# Power_Management.net
KiCad netlist of a schematic drawn in Altium Designer
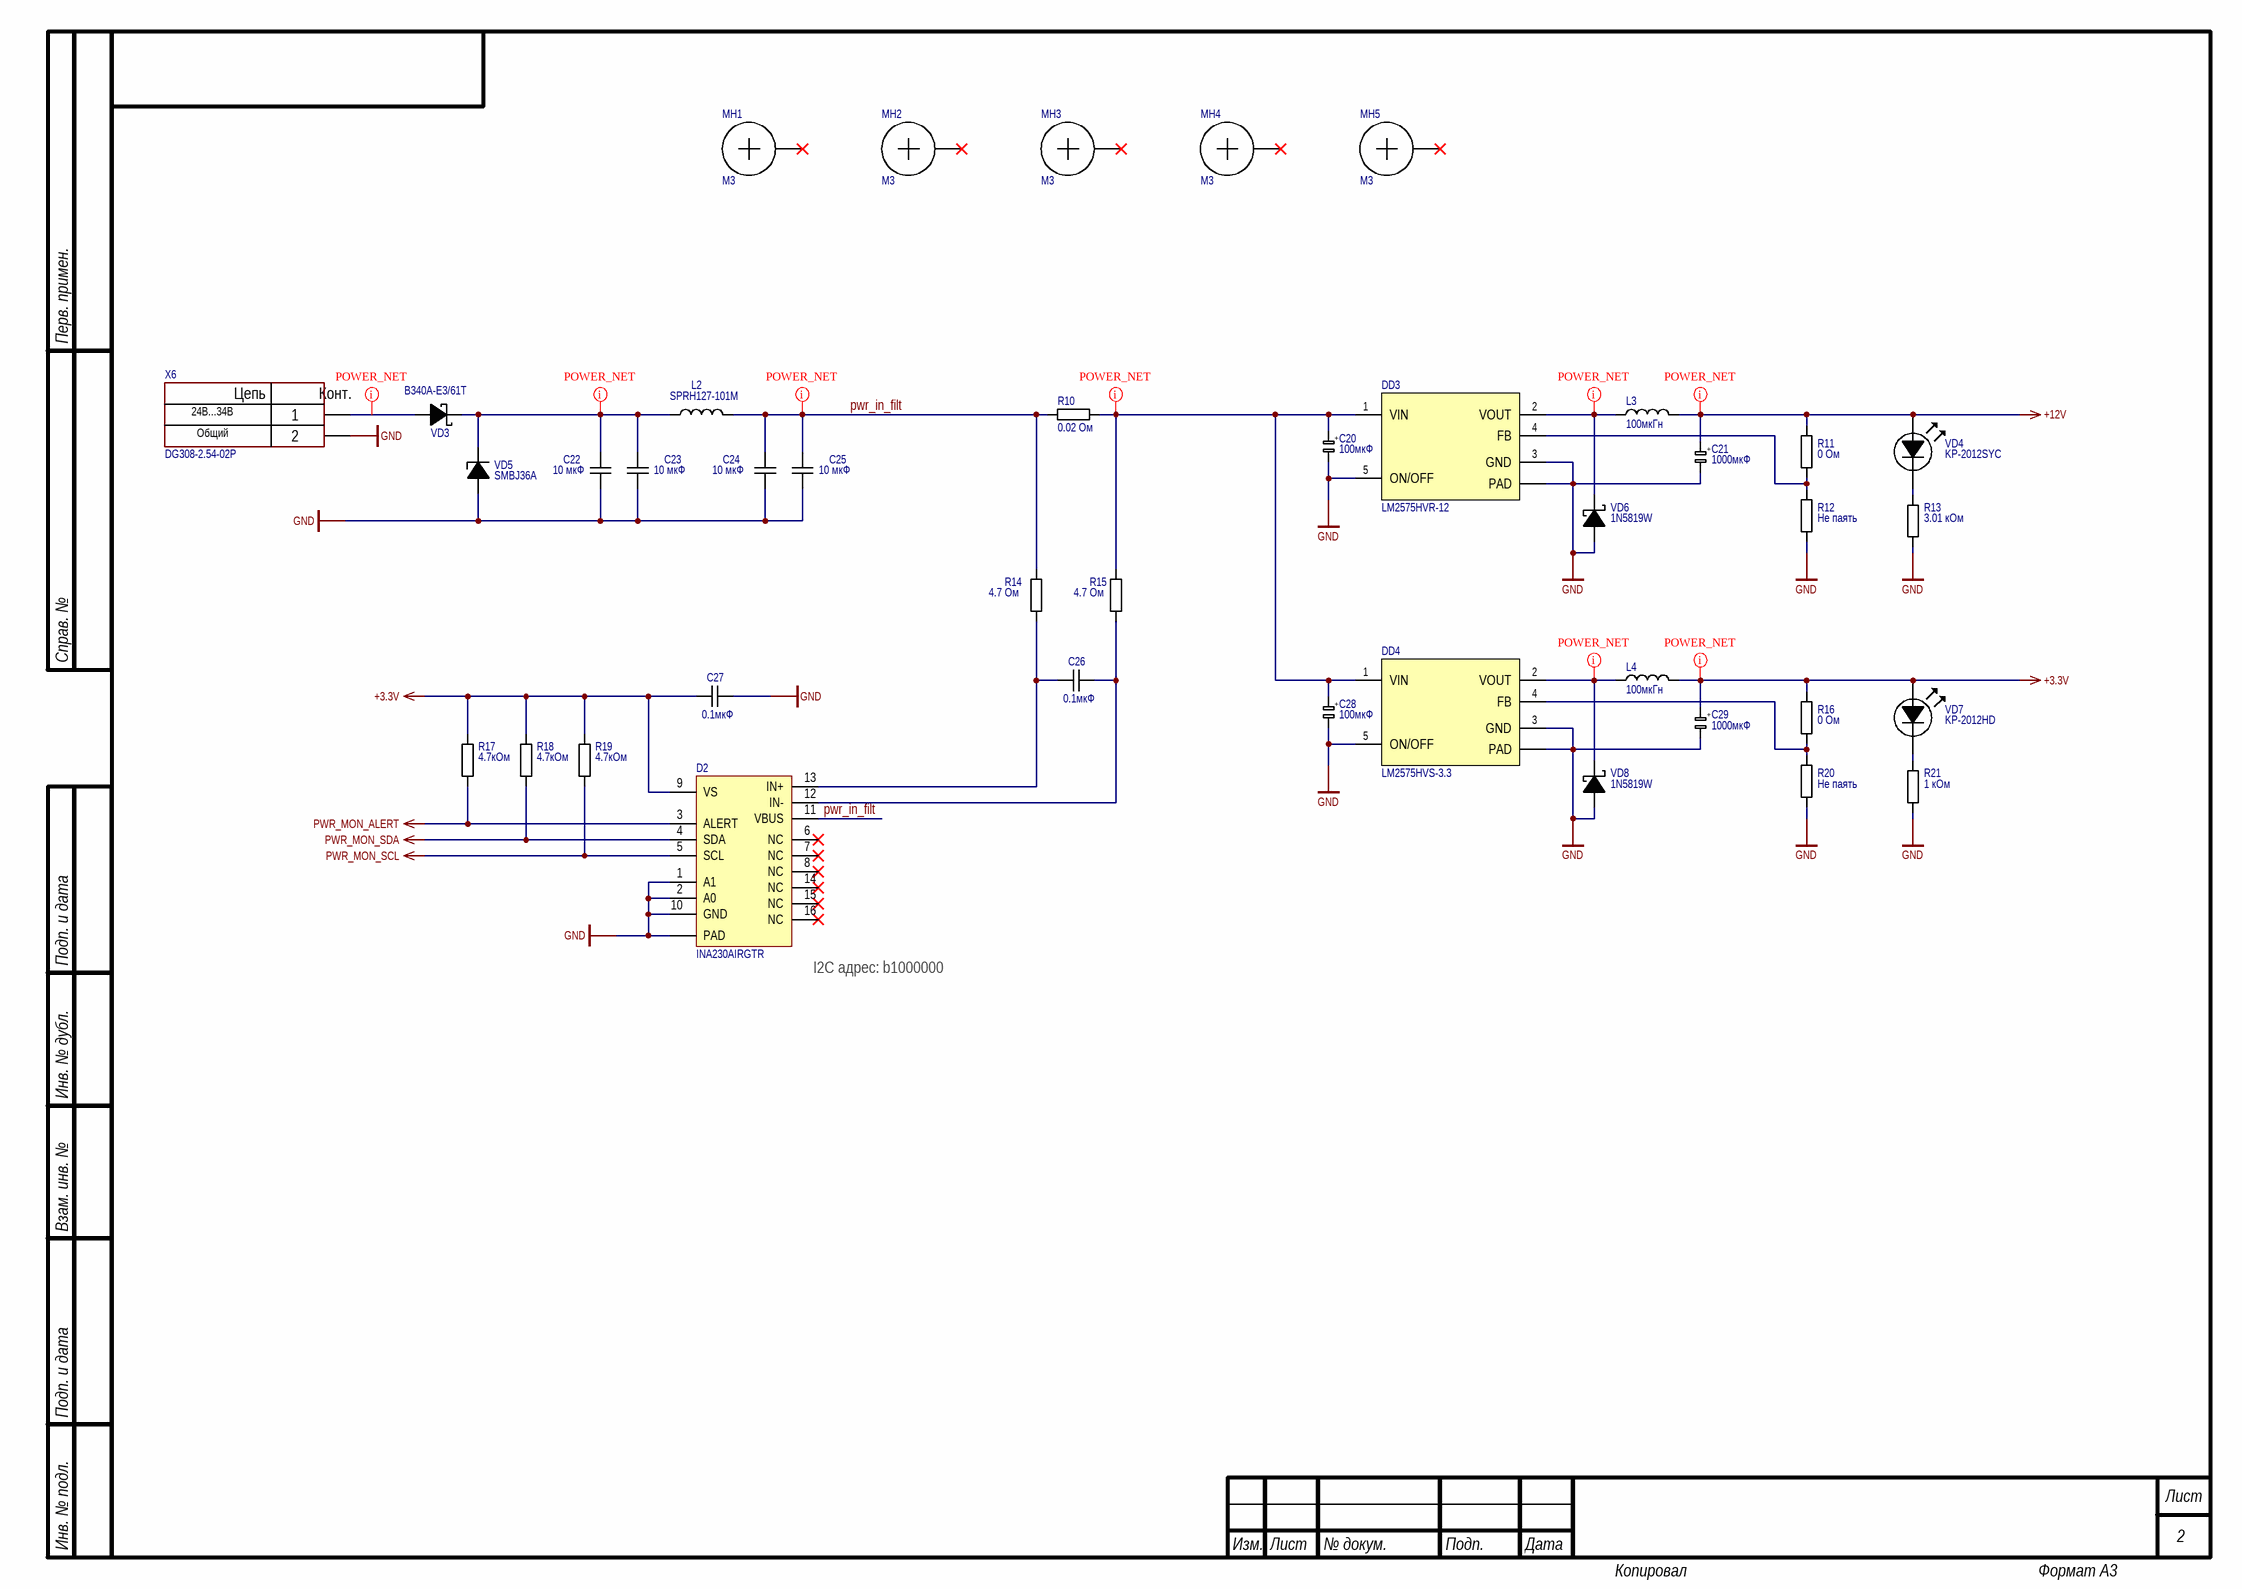
[diagram p0: Power_Management.SchDoc]

(export (version "E")
  (design (tool "Eeschema 10.0.6"))
  (components
    (comp (ref "C20")
      (value "100мкФ")
      (footprint "PiezoControlBoard:CAP_RADIAL_10x20_P5")
      (fields
        (field (name "TOLERANCE") "20%")
        (field (name "VOLTAGE") "100В")
        (field (name "MANUFACTURER PART NUMBER") "JRB2A101M05001000200000B")
      )
      (libsource (lib "PiezoControlBoard") (part "JRB2A101M05001000200000B"))
    )
    (comp (ref "C21")
      (value "1000мкФ")
      (footprint "PiezoControlBoard:CAP_RADIAL_10x20_P5")
      (fields
        (field (name "TOLERANCE") "20%")
        (field (name "VOLTAGE") "25В")
        (field (name "MANUFACTURER PART NUMBER") "JRB1E102M05001000210000B")
      )
      (libsource (lib "PiezoControlBoard") (part "JRB1E102M05001000210000B"))
    )
    (comp (ref "C22")
      (value "10 мкФ")
      (footprint "CAP_1206")
      (description "Конденсатор")
      (fields (field (name "TOLERANCE") "10%") (field (name "VOLTAGE") "50 В"))
      (libsource (lib "load") (part "Cap_1206"))
    )
    (comp (ref "C23")
      (value "10 мкФ")
      (footprint "CAP_1206")
      (description "Конденсатор")
      (fields (field (name "TOLERANCE") "10%") (field (name "VOLTAGE") "50 В"))
      (libsource (lib "load") (part "Cap_1206"))
    )
    (comp (ref "C24")
      (value "10 мкФ")
      (footprint "CAP_1206")
      (description "Конденсатор")
      (fields (field (name "TOLERANCE") "10%") (field (name "VOLTAGE") "50 В"))
      (libsource (lib "load") (part "Cap_1206"))
    )
    (comp (ref "C25")
      (value "10 мкФ")
      (footprint "CAP_1206")
      (description "Конденсатор")
      (fields (field (name "TOLERANCE") "10%") (field (name "VOLTAGE") "50 В"))
      (libsource (lib "load") (part "Cap_1206"))
    )
    (comp (ref "C26")
      (value "0.1мкФ")
      (footprint "CAP-0603")
      (description "Конденсатор")
      (fields (field (name "TOLERANCE") "10%") (field (name "VOLTAGE") "50В"))
      (libsource (lib "load") (part "Cap_0603"))
    )
    (comp (ref "C27")
      (value "0.1мкФ")
      (footprint "CAP-0603")
      (description "Конденсатор")
      (fields (field (name "TOLERANCE") "10%") (field (name "VOLTAGE") "50В"))
      (libsource (lib "load") (part "Cap_0603"))
    )
    (comp (ref "C28")
      (value "100мкФ")
      (footprint "PiezoControlBoard:CAP_RADIAL_10x20_P5")
      (fields
        (field (name "TOLERANCE") "20%")
        (field (name "VOLTAGE") "100В")
        (field (name "MANUFACTURER PART NUMBER") "JRB2A101M05001000200000B")
      )
      (libsource (lib "PiezoControlBoard") (part "JRB2A101M05001000200000B"))
    )
    (comp (ref "C29")
      (value "1000мкФ")
      (footprint "PiezoControlBoard:CAP_RADIAL_10x20_P5")
      (fields
        (field (name "TOLERANCE") "20%")
        (field (name "VOLTAGE") "25В")
        (field (name "MANUFACTURER PART NUMBER") "JRB1E102M05001000210000B")
      )
      (libsource (lib "PiezoControlBoard") (part "JRB1E102M05001000210000B"))
    )
    (comp (ref "D2")
      (value "INA230AIRGTR")
      (footprint "VQFN-16")
      (description "36-V, 16-bit, I²C output current, voltage and power monitor with alert 16-VQFN -40 to 125")
      (fields (field (name "MANUFACTURER") "Texas Instruments"))
      (libsource (lib "power") (part "INA230AIRGTR"))
    )
    (comp (ref "DD3")
      (value "LM2575HVR-12")
      (footprint "PiezoControlBoard:TO-263-5")
      (libsource (lib "PiezoControlBoard") (part "LM2575HVR-12"))
    )
    (comp (ref "DD4")
      (value "LM2575HVS-3.3")
      (footprint "PiezoControlBoard:TO-263-5")
      (description "LM2575HVS-3.3, Понижающий DC-DC преобразователь, Uвх=до 60В, Uвых=3.3В, 1А, 52кГц [TO-263-5L]")
      (libsource (lib "PiezoControlBoard") (part "LM2575HVS-3.3"))
    )
    (comp (ref "L2")
      (value "SPRH127-101M")
      (footprint "IND_SPRH127-101M")
      (description "SMD Low Loss Power Inductor")
      (fields (field (name "MANUFACTURER") "Codaca"))
      (libsource (lib "PiezoControlBoard") (part "SPRH127-101M"))
    )
    (comp (ref "L3")
      (value "100мкГн")
      (footprint "PiezoControlBoard:IND_10.4X10.4")
      (description "Inductor Power Shielded Wirewound 100uH 20% 100KHz Ferrite 1.05A 0.22Ohm DCR Automotive T/R")
      (fields
        (field (name "MANUFACTURER") "EPCOS")
        (field (name "MANUFACTURER PART NUMBER") "B82464G4104M000")
      )
      (libsource (lib "PiezoControlBoard") (part "B82464G4104M000"))
    )
    (comp (ref "L4")
      (value "100мкГн")
      (footprint "PiezoControlBoard:IND_10.4X10.4")
      (description "Inductor Power Shielded Wirewound 100uH 20% 100KHz Ferrite 1.05A 0.22Ohm DCR Automotive T/R")
      (fields
        (field (name "MANUFACTURER") "EPCOS")
        (field (name "MANUFACTURER PART NUMBER") "B82464G4104M000")
      )
      (libsource (lib "PiezoControlBoard") (part "B82464G4104M000"))
    )
    (comp (ref "MH1")
      (value "M3")
      (footprint "M3")
      (description "отверстие М3")
      (libsource (lib "mechanical") (part "M3"))
    )
    (comp (ref "MH2")
      (value "M3")
      (footprint "M3")
      (description "отверстие М3")
      (libsource (lib "mechanical") (part "M3"))
    )
    (comp (ref "MH3")
      (value "M3")
      (footprint "M3")
      (description "отверстие М3")
      (libsource (lib "mechanical") (part "M3"))
    )
    (comp (ref "MH4")
      (value "M3")
      (footprint "M3")
      (description "отверстие М3")
      (libsource (lib "mechanical") (part "M3"))
    )
    (comp (ref "MH5")
      (value "M3")
      (footprint "M3")
      (description "отверстие М3")
      (libsource (lib "mechanical") (part "M3"))
    )
    (comp (ref "R10")
      (value "0.02 Ом")
      (footprint "RES-2512")
      (description "Резистор")
      (fields (field (name "POWER") "3 Вт") (field (name "TOLERANCE") "1%"))
      (libsource (lib "load") (part "Res_2512"))
    )
    (comp (ref "R11")
      (value "0 Ом")
      (footprint "RES-0402")
      (description "Резистор")
      (fields (field (name "TOLERANCE") "5%") (field (name "POWER") "0.062 Вт"))
      (libsource (lib "load") (part "Res_0402"))
    )
    (comp (ref "R12")
      (value "Не паять")
      (footprint "RES-0402")
      (description "Резистор")
      (fields (field (name "Comment") "RES-Не паять-----0402"))
      (libsource (lib "load") (part "Res_0402"))
    )
    (comp (ref "R13")
      (value "3.01 кОм")
      (footprint "RES-0805")
      (description "Резистор")
      (fields (field (name "POWER") "0.125Вт") (field (name "TOLERANCE") "1%"))
      (libsource (lib "load") (part "Res_0805"))
    )
    (comp (ref "R14")
      (value "4.7 Ом")
      (footprint "RES-0402")
      (description "Резистор")
      (fields (field (name "TOLERANCE") "5%") (field (name "POWER") "0.062 Вт"))
      (libsource (lib "load") (part "Res_0402"))
    )
    (comp (ref "R15")
      (value "4.7 Ом")
      (footprint "RES-0402")
      (description "Резистор")
      (fields (field (name "TOLERANCE") "5%") (field (name "POWER") "0.062 Вт"))
      (libsource (lib "load") (part "Res_0402"))
    )
    (comp (ref "R16")
      (value "0 Ом")
      (footprint "RES-0402")
      (description "Резистор")
      (fields (field (name "TOLERANCE") "5%") (field (name "POWER") "0.062 Вт"))
      (libsource (lib "load") (part "Res_0402"))
    )
    (comp (ref "R17")
      (value "4.7кОм")
      (footprint "RES-0402")
      (description "Резистор")
      (fields (field (name "TOLERANCE") "5%") (field (name "POWER") "0.062Вт"))
      (libsource (lib "load") (part "Res_0402"))
    )
    (comp (ref "R18")
      (value "4.7кОм")
      (footprint "RES-0402")
      (description "Резистор")
      (fields (field (name "TOLERANCE") "5%") (field (name "POWER") "0.062Вт"))
      (libsource (lib "load") (part "Res_0402"))
    )
    (comp (ref "R19")
      (value "4.7кОм")
      (footprint "RES-0402")
      (description "Резистор")
      (fields (field (name "TOLERANCE") "5%") (field (name "POWER") "0.062Вт"))
      (libsource (lib "load") (part "Res_0402"))
    )
    (comp (ref "R20")
      (value "Не паять")
      (footprint "RES-0402")
      (description "Резистор")
      (fields (field (name "Comment") "RES-Не паять-----0402"))
      (libsource (lib "load") (part "Res_0402"))
    )
    (comp (ref "R21")
      (value "1 кОм")
      (footprint "RES-0805")
      (description "Резистор")
      (fields (field (name "POWER") "0.125Вт") (field (name "TOLERANCE") "1%"))
      (libsource (lib "load") (part "Res_0805"))
    )
    (comp (ref "VD3")
      (value "B340A-E3/61T")
      (footprint "PiezoControlBoard:DO-214AC")
      (description "Rectifier Diode, Schottky, 1 Phase, 1 Element, 3A, 40V V(RRM), Silicon, DO-214AC")
      (fields (field (name "MANUFACTURER") "Vishay Semiconductors"))
      (libsource (lib "PiezoControlBoard") (part "B340A-E3/61T"))
    )
    (comp (ref "VD4")
      (value "KP-2012SYC")
      (footprint "LED 0805")
      (description "LED SMD 0805")
      (libsource (lib "PiezoControlBoard") (part "LED 0805"))
    )
    (comp (ref "VD5")
      (value "SMBJ36A")
      (footprint "PiezoControlBoard:DO-214AA")
      (description "SMBJ36A, Защитный диод 600Вт 36В [SMB / DO-214AA]")
      (libsource (lib "PiezoControlBoard") (part "SMBJ36A"))
    )
    (comp (ref "VD6")
      (value "1N5819W")
      (footprint "SOD-123")
      (description "Диод Шоттки 40В 1А")
      (libsource (lib "PiezoControlBoard") (part "1N5819W"))
    )
    (comp (ref "VD7")
      (value "KP-2012HD")
      (footprint "LED 0805")
      (description "LED SMD 0805")
      (libsource (lib "PiezoControlBoard") (part "LED 0805"))
    )
    (comp (ref "VD8")
      (value "1N5819W")
      (footprint "SOD-123")
      (description "Диод Шоттки 40В 1А")
      (libsource (lib "PiezoControlBoard") (part "1N5819W"))
    )
    (comp (ref "X6")
      (value "DG308-2.54-02P")
      (footprint "PiezoControlBoard:DG30825402P1400AH")
      (fields (field (name "CURCIUT 2") "Общий") (field (name "CURCIUT 1") "24В...34В"))
      (libsource (lib "PiezoControlBoard") (part "DG308-2.54-02P"))
    )
  )
  (nets
    (net (code "1") (name "+3.3V") (class "Default")
      (node (ref "C27") (pin "1") (pinfunction "1_1") (pintype "passive"))
      (node (ref "C29") (pin "P") (pinfunction "P_P") (pintype "passive"))
      (node (ref "D2") (pin "9") (pinfunction "VS_9") (pintype "passive"))
      (node (ref "L4") (pin "2") (pinfunction "2_2") (pintype "passive"))
      (node (ref "R16") (pin "2") (pinfunction "2_2") (pintype "passive"))
      (node (ref "R17") (pin "2") (pinfunction "2_2") (pintype "passive"))
      (node (ref "R18") (pin "2") (pinfunction "2_2") (pintype "passive"))
      (node (ref "R19") (pin "2") (pinfunction "2_2") (pintype "passive"))
      (node (ref "VD7") (pin "1") (pinfunction "A_1") (pintype "passive"))
    )
    (net (code "2") (name "+12V") (class "Default")
      (node (ref "C21") (pin "P") (pinfunction "P_P") (pintype "passive"))
      (node (ref "L3") (pin "2") (pinfunction "2_2") (pintype "passive"))
      (node (ref "R11") (pin "2") (pinfunction "2_2") (pintype "passive"))
      (node (ref "VD4") (pin "1") (pinfunction "A_1") (pintype "passive"))
    )
    (net (code "3") (name "/pwr_in_filt") (class "Default")
      (node (ref "C24") (pin "2") (pinfunction "2_2") (pintype "passive"))
      (node (ref "C25") (pin "2") (pinfunction "2_2") (pintype "passive"))
      (node (ref "D2") (pin "11") (pinfunction "VBUS_11") (pintype "passive"))
      (node (ref "L2") (pin "2") (pinfunction "2_2") (pintype "passive"))
      (node (ref "R10") (pin "1") (pinfunction "1_1") (pintype "passive"))
      (node (ref "R14") (pin "2") (pinfunction "2_2") (pintype "passive"))
    )
    (net (code "4") (name "GND") (class "Default")
      (node (ref "C20") (pin "N") (pinfunction "N_N") (pintype "passive"))
      (node (ref "C21") (pin "N") (pinfunction "N_N") (pintype "passive"))
      (node (ref "C22") (pin "1") (pinfunction "1_1") (pintype "passive"))
      (node (ref "C23") (pin "1") (pinfunction "1_1") (pintype "passive"))
      (node (ref "C24") (pin "1") (pinfunction "1_1") (pintype "passive"))
      (node (ref "C25") (pin "1") (pinfunction "1_1") (pintype "passive"))
      (node (ref "C27") (pin "2") (pinfunction "2_2") (pintype "passive"))
      (node (ref "C28") (pin "N") (pinfunction "N_N") (pintype "passive"))
      (node (ref "C29") (pin "N") (pinfunction "N_N") (pintype "passive"))
      (node (ref "D2") (pin "1") (pinfunction "A1_1") (pintype "passive"))
      (node (ref "D2") (pin "10") (pinfunction "GND_10") (pintype "passive"))
      (node (ref "D2") (pin "2") (pinfunction "A0_2") (pintype "passive"))
      (node (ref "D2") (pin "PAD") (pinfunction "PAD_PAD") (pintype "passive"))
      (node (ref "DD3") (pin "3") (pinfunction "GND_3") (pintype "passive"))
      (node (ref "DD3") (pin "5") (pinfunction "ON/OFF_5") (pintype "passive"))
      (node (ref "DD3") (pin "PAD") (pinfunction "PAD_PAD") (pintype "passive"))
      (node (ref "DD4") (pin "3") (pinfunction "GND_3") (pintype "passive"))
      (node (ref "DD4") (pin "5") (pinfunction "ON/OFF_5") (pintype "passive"))
      (node (ref "DD4") (pin "PAD") (pinfunction "PAD_PAD") (pintype "passive"))
      (node (ref "R12") (pin "1") (pinfunction "1_1") (pintype "passive"))
      (node (ref "R13") (pin "1") (pinfunction "1_1") (pintype "passive"))
      (node (ref "R20") (pin "1") (pinfunction "1_1") (pintype "passive"))
      (node (ref "R21") (pin "1") (pinfunction "1_1") (pintype "passive"))
      (node (ref "VD5") (pin "A") (pinfunction "A_A") (pintype "passive"))
      (node (ref "VD6") (pin "1") (pinfunction "A_1") (pintype "passive"))
      (node (ref "VD8") (pin "1") (pinfunction "A_1") (pintype "passive"))
      (node (ref "X6") (pin "2") (pinfunction "2_2") (pintype "passive"))
    )
    (net (code "5") (name "Net-(C22-Pad2)") (class "Default")
      (node (ref "C22") (pin "2") (pinfunction "2_2") (pintype "passive"))
      (node (ref "C23") (pin "2") (pinfunction "2_2") (pintype "passive"))
      (node (ref "L2") (pin "1") (pinfunction "1_1") (pintype "passive"))
      (node (ref "VD3") (pin "C") (pinfunction "C_C") (pintype "passive"))
      (node (ref "VD5") (pin "C") (pinfunction "C_C") (pintype "passive"))
    )
    (net (code "6") (name "Net-(D2-IN+)") (class "Default")
      (node (ref "C26") (pin "1") (pinfunction "1_1") (pintype "passive"))
      (node (ref "D2") (pin "13") (pinfunction "IN+_13") (pintype "passive"))
      (node (ref "R14") (pin "1") (pinfunction "1_1") (pintype "passive"))
    )
    (net (code "7") (name "Net-(D2-IN-)") (class "Default")
      (node (ref "C26") (pin "2") (pinfunction "2_2") (pintype "passive"))
      (node (ref "D2") (pin "12") (pinfunction "IN-_12") (pintype "passive"))
      (node (ref "R15") (pin "1") (pinfunction "1_1") (pintype "passive"))
    )
    (net (code "8") (name "Net-(DD3-FB)") (class "Default")
      (node (ref "DD3") (pin "4") (pinfunction "FB_4") (pintype "passive"))
      (node (ref "R11") (pin "1") (pinfunction "1_1") (pintype "passive"))
      (node (ref "R12") (pin "2") (pinfunction "2_2") (pintype "passive"))
    )
    (net (code "9") (name "Net-(DD3-VIN)") (class "Default")
      (node (ref "C20") (pin "P") (pinfunction "P_P") (pintype "passive"))
      (node (ref "C28") (pin "P") (pinfunction "P_P") (pintype "passive"))
      (node (ref "DD3") (pin "1") (pinfunction "VIN_1") (pintype "passive"))
      (node (ref "DD4") (pin "1") (pinfunction "VIN_1") (pintype "passive"))
      (node (ref "R10") (pin "2") (pinfunction "2_2") (pintype "passive"))
      (node (ref "R15") (pin "2") (pinfunction "2_2") (pintype "passive"))
    )
    (net (code "10") (name "Net-(DD3-VOUT)") (class "Default")
      (node (ref "DD3") (pin "2") (pinfunction "VOUT_2") (pintype "passive"))
      (node (ref "L3") (pin "1") (pinfunction "1_1") (pintype "passive"))
      (node (ref "VD6") (pin "2") (pinfunction "K_2") (pintype "passive"))
    )
    (net (code "11") (name "Net-(DD4-FB)") (class "Default")
      (node (ref "DD4") (pin "4") (pinfunction "FB_4") (pintype "passive"))
      (node (ref "R16") (pin "1") (pinfunction "1_1") (pintype "passive"))
      (node (ref "R20") (pin "2") (pinfunction "2_2") (pintype "passive"))
    )
    (net (code "12") (name "Net-(DD4-VOUT)") (class "Default")
      (node (ref "DD4") (pin "2") (pinfunction "VOUT_2") (pintype "passive"))
      (node (ref "L4") (pin "1") (pinfunction "1_1") (pintype "passive"))
      (node (ref "VD8") (pin "2") (pinfunction "K_2") (pintype "passive"))
    )
    (net (code "13") (name "Net-(VD3-PadA)") (class "Default")
      (node (ref "VD3") (pin "A") (pinfunction "A_A") (pintype "passive"))
      (node (ref "X6") (pin "1") (pinfunction "1_1") (pintype "passive"))
    )
    (net (code "14") (name "Net-(VD4-C)") (class "Default")
      (node (ref "R13") (pin "2") (pinfunction "2_2") (pintype "passive"))
      (node (ref "VD4") (pin "2") (pinfunction "C_2") (pintype "passive"))
    )
    (net (code "15") (name "Net-(VD7-C)") (class "Default")
      (node (ref "R21") (pin "2") (pinfunction "2_2") (pintype "passive"))
      (node (ref "VD7") (pin "2") (pinfunction "C_2") (pintype "passive"))
    )
    (net (code "16") (name "PWR_MON_ALERT") (class "Default")
      (node (ref "D2") (pin "3") (pinfunction "ALERT_3") (pintype "passive"))
      (node (ref "R17") (pin "1") (pinfunction "1_1") (pintype "passive"))
    )
    (net (code "17") (name "PWR_MON_SCL") (class "Default")
      (node (ref "D2") (pin "5") (pinfunction "SCL_5") (pintype "passive"))
      (node (ref "R19") (pin "1") (pinfunction "1_1") (pintype "passive"))
    )
    (net (code "18") (name "PWR_MON_SDA") (class "Default")
      (node (ref "D2") (pin "4") (pinfunction "SDA_4") (pintype "passive"))
      (node (ref "R18") (pin "1") (pinfunction "1_1") (pintype "passive"))
    )
    (net (code "19") (name "unconnected-(D2-NC-Pad6)") (class "Default")
      (node (ref "D2") (pin "6") (pinfunction "NC_6") (pintype "passive+no_connect"))
    )
    (net (code "20") (name "unconnected-(D2-NC-Pad7)") (class "Default")
      (node (ref "D2") (pin "7") (pinfunction "NC_7") (pintype "passive+no_connect"))
    )
    (net (code "21") (name "unconnected-(D2-NC-Pad8)") (class "Default")
      (node (ref "D2") (pin "8") (pinfunction "NC_8") (pintype "passive+no_connect"))
    )
    (net (code "22") (name "unconnected-(D2-NC-Pad14)") (class "Default")
      (node (ref "D2") (pin "14") (pinfunction "NC_14") (pintype "passive+no_connect"))
    )
    (net (code "23") (name "unconnected-(D2-NC-Pad15)") (class "Default")
      (node (ref "D2") (pin "15") (pinfunction "NC_15") (pintype "passive+no_connect"))
    )
    (net (code "24") (name "unconnected-(D2-NC-Pad16)") (class "Default")
      (node (ref "D2") (pin "16") (pinfunction "NC_16") (pintype "passive+no_connect"))
    )
    (net (code "25") (name "unconnected-(MH1-Pad1)") (class "Default")
      (node (ref "MH1") (pin "1") (pinfunction "1_1") (pintype "passive+no_connect"))
    )
    (net (code "26") (name "unconnected-(MH2-Pad1)") (class "Default")
      (node (ref "MH2") (pin "1") (pinfunction "1_1") (pintype "passive+no_connect"))
    )
    (net (code "27") (name "unconnected-(MH3-Pad1)") (class "Default")
      (node (ref "MH3") (pin "1") (pinfunction "1_1") (pintype "passive+no_connect"))
    )
    (net (code "28") (name "unconnected-(MH4-Pad1)") (class "Default")
      (node (ref "MH4") (pin "1") (pinfunction "1_1") (pintype "passive+no_connect"))
    )
    (net (code "29") (name "unconnected-(MH5-Pad1)") (class "Default")
      (node (ref "MH5") (pin "1") (pinfunction "1_1") (pintype "passive+no_connect"))
    )
  )
)
